# l298_updated.net
KiCad netlist of a schematic drawn in EAGLE
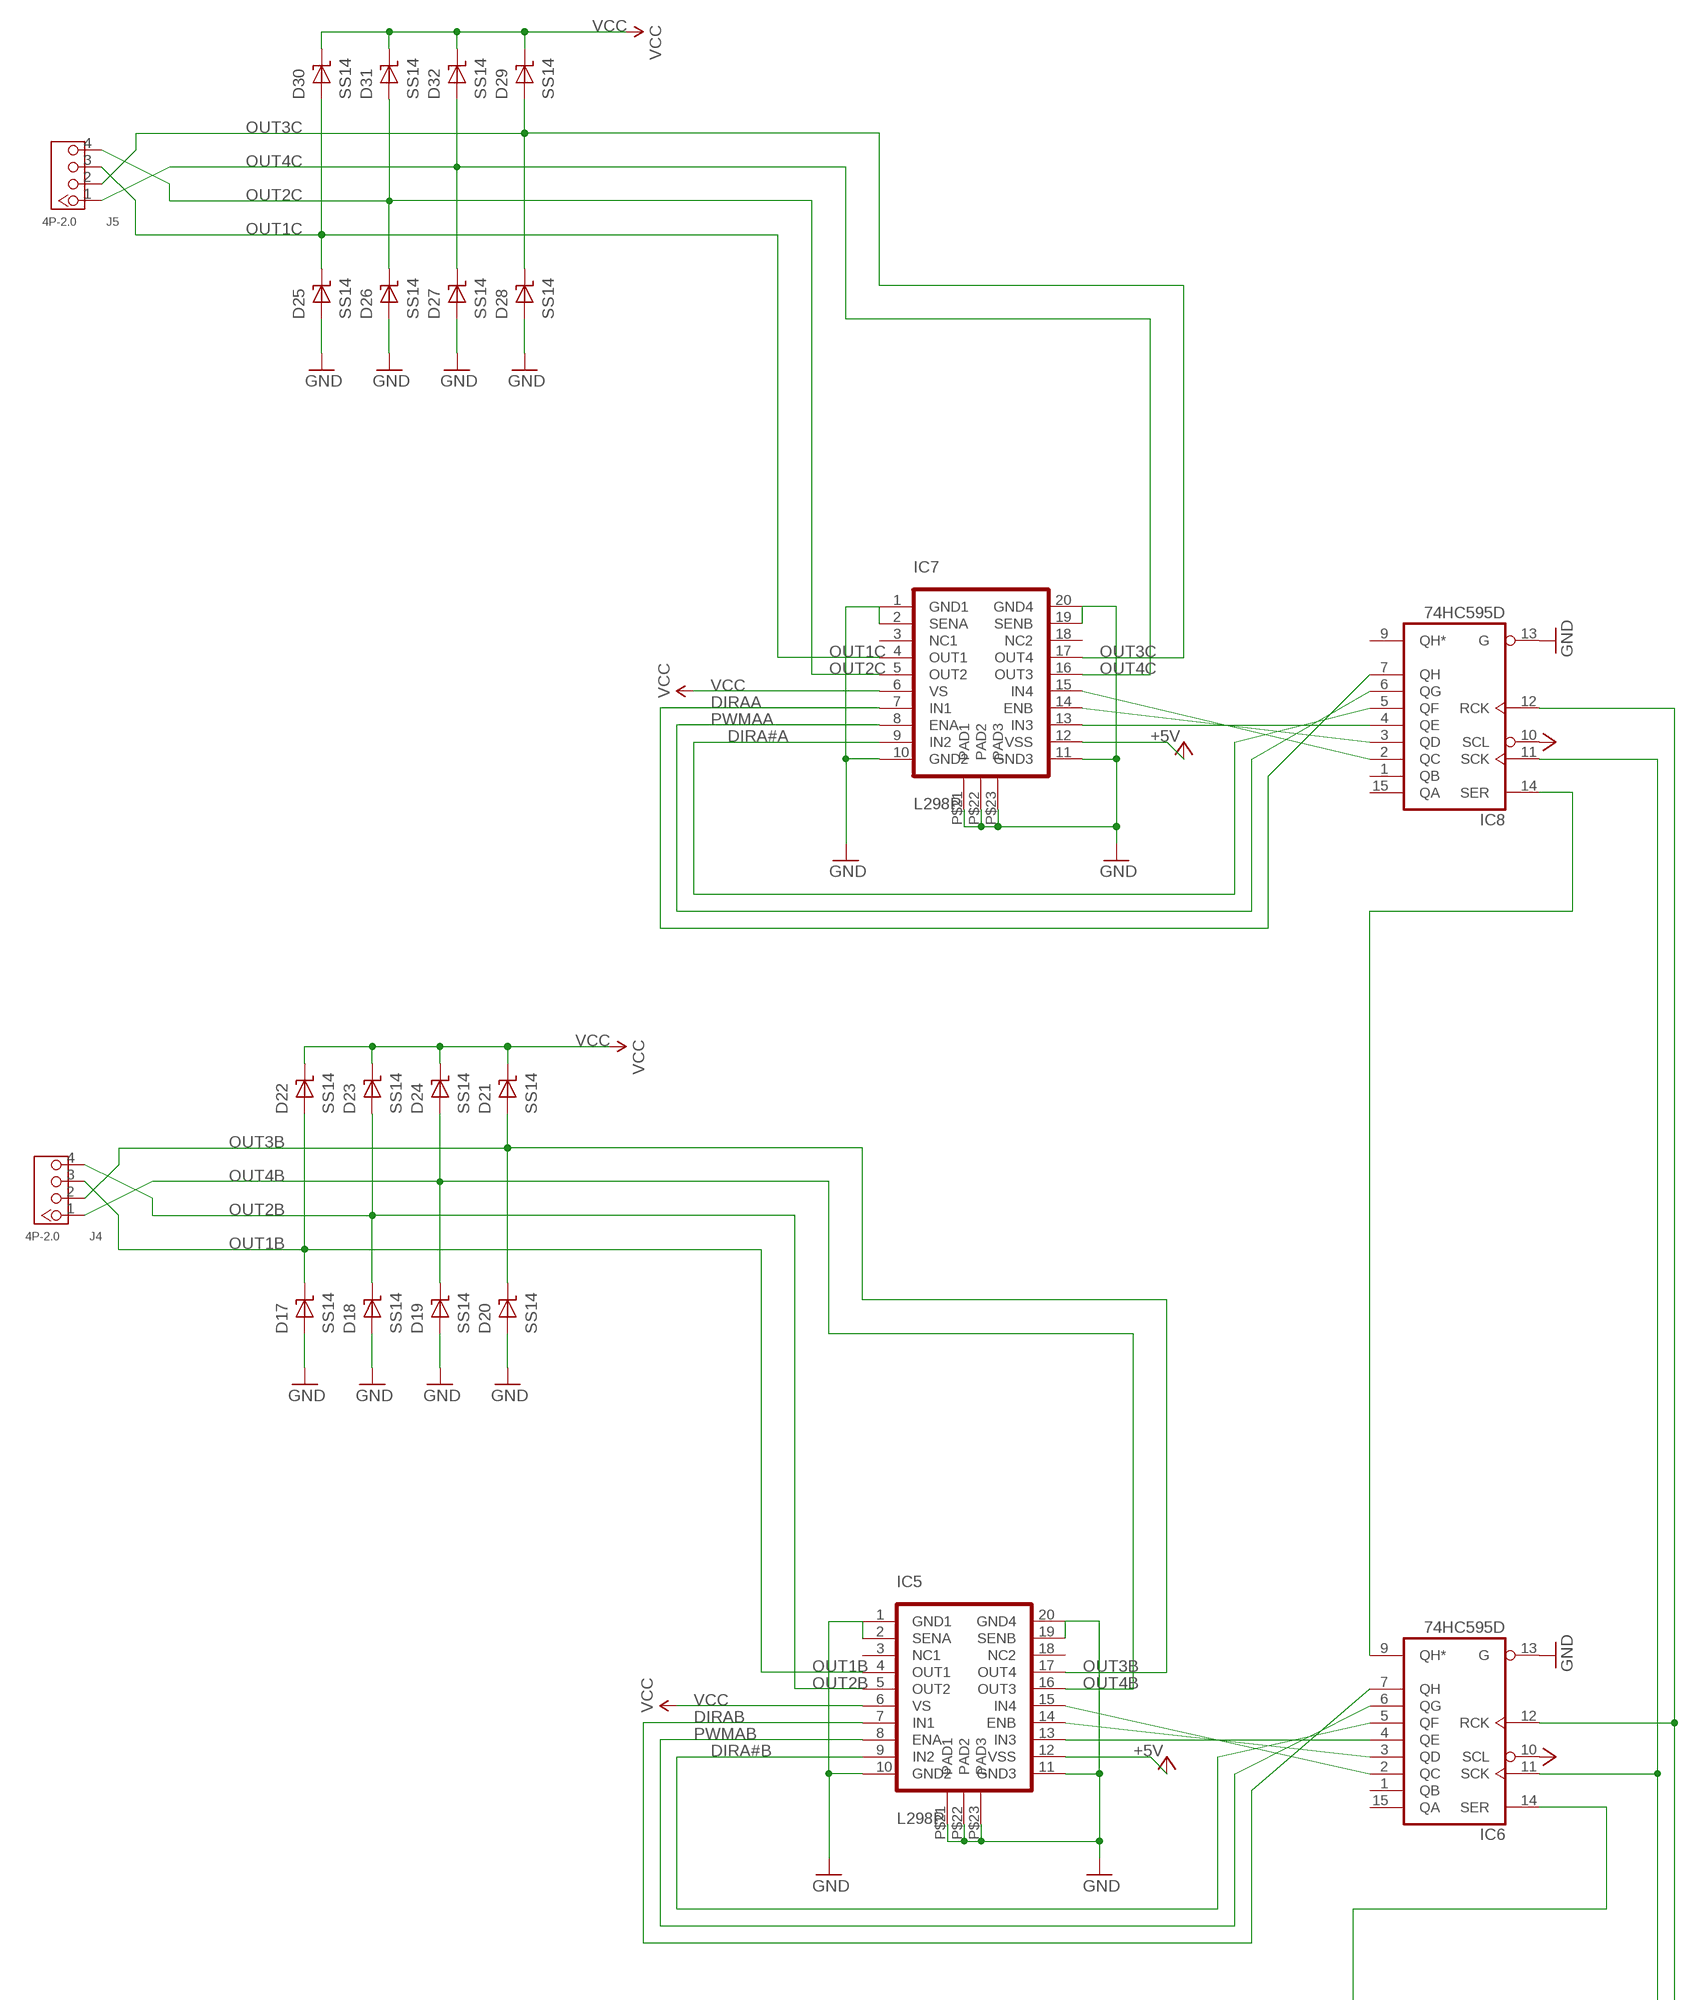
[diagram p0: schematic, sheet 1, part 1 of 2]
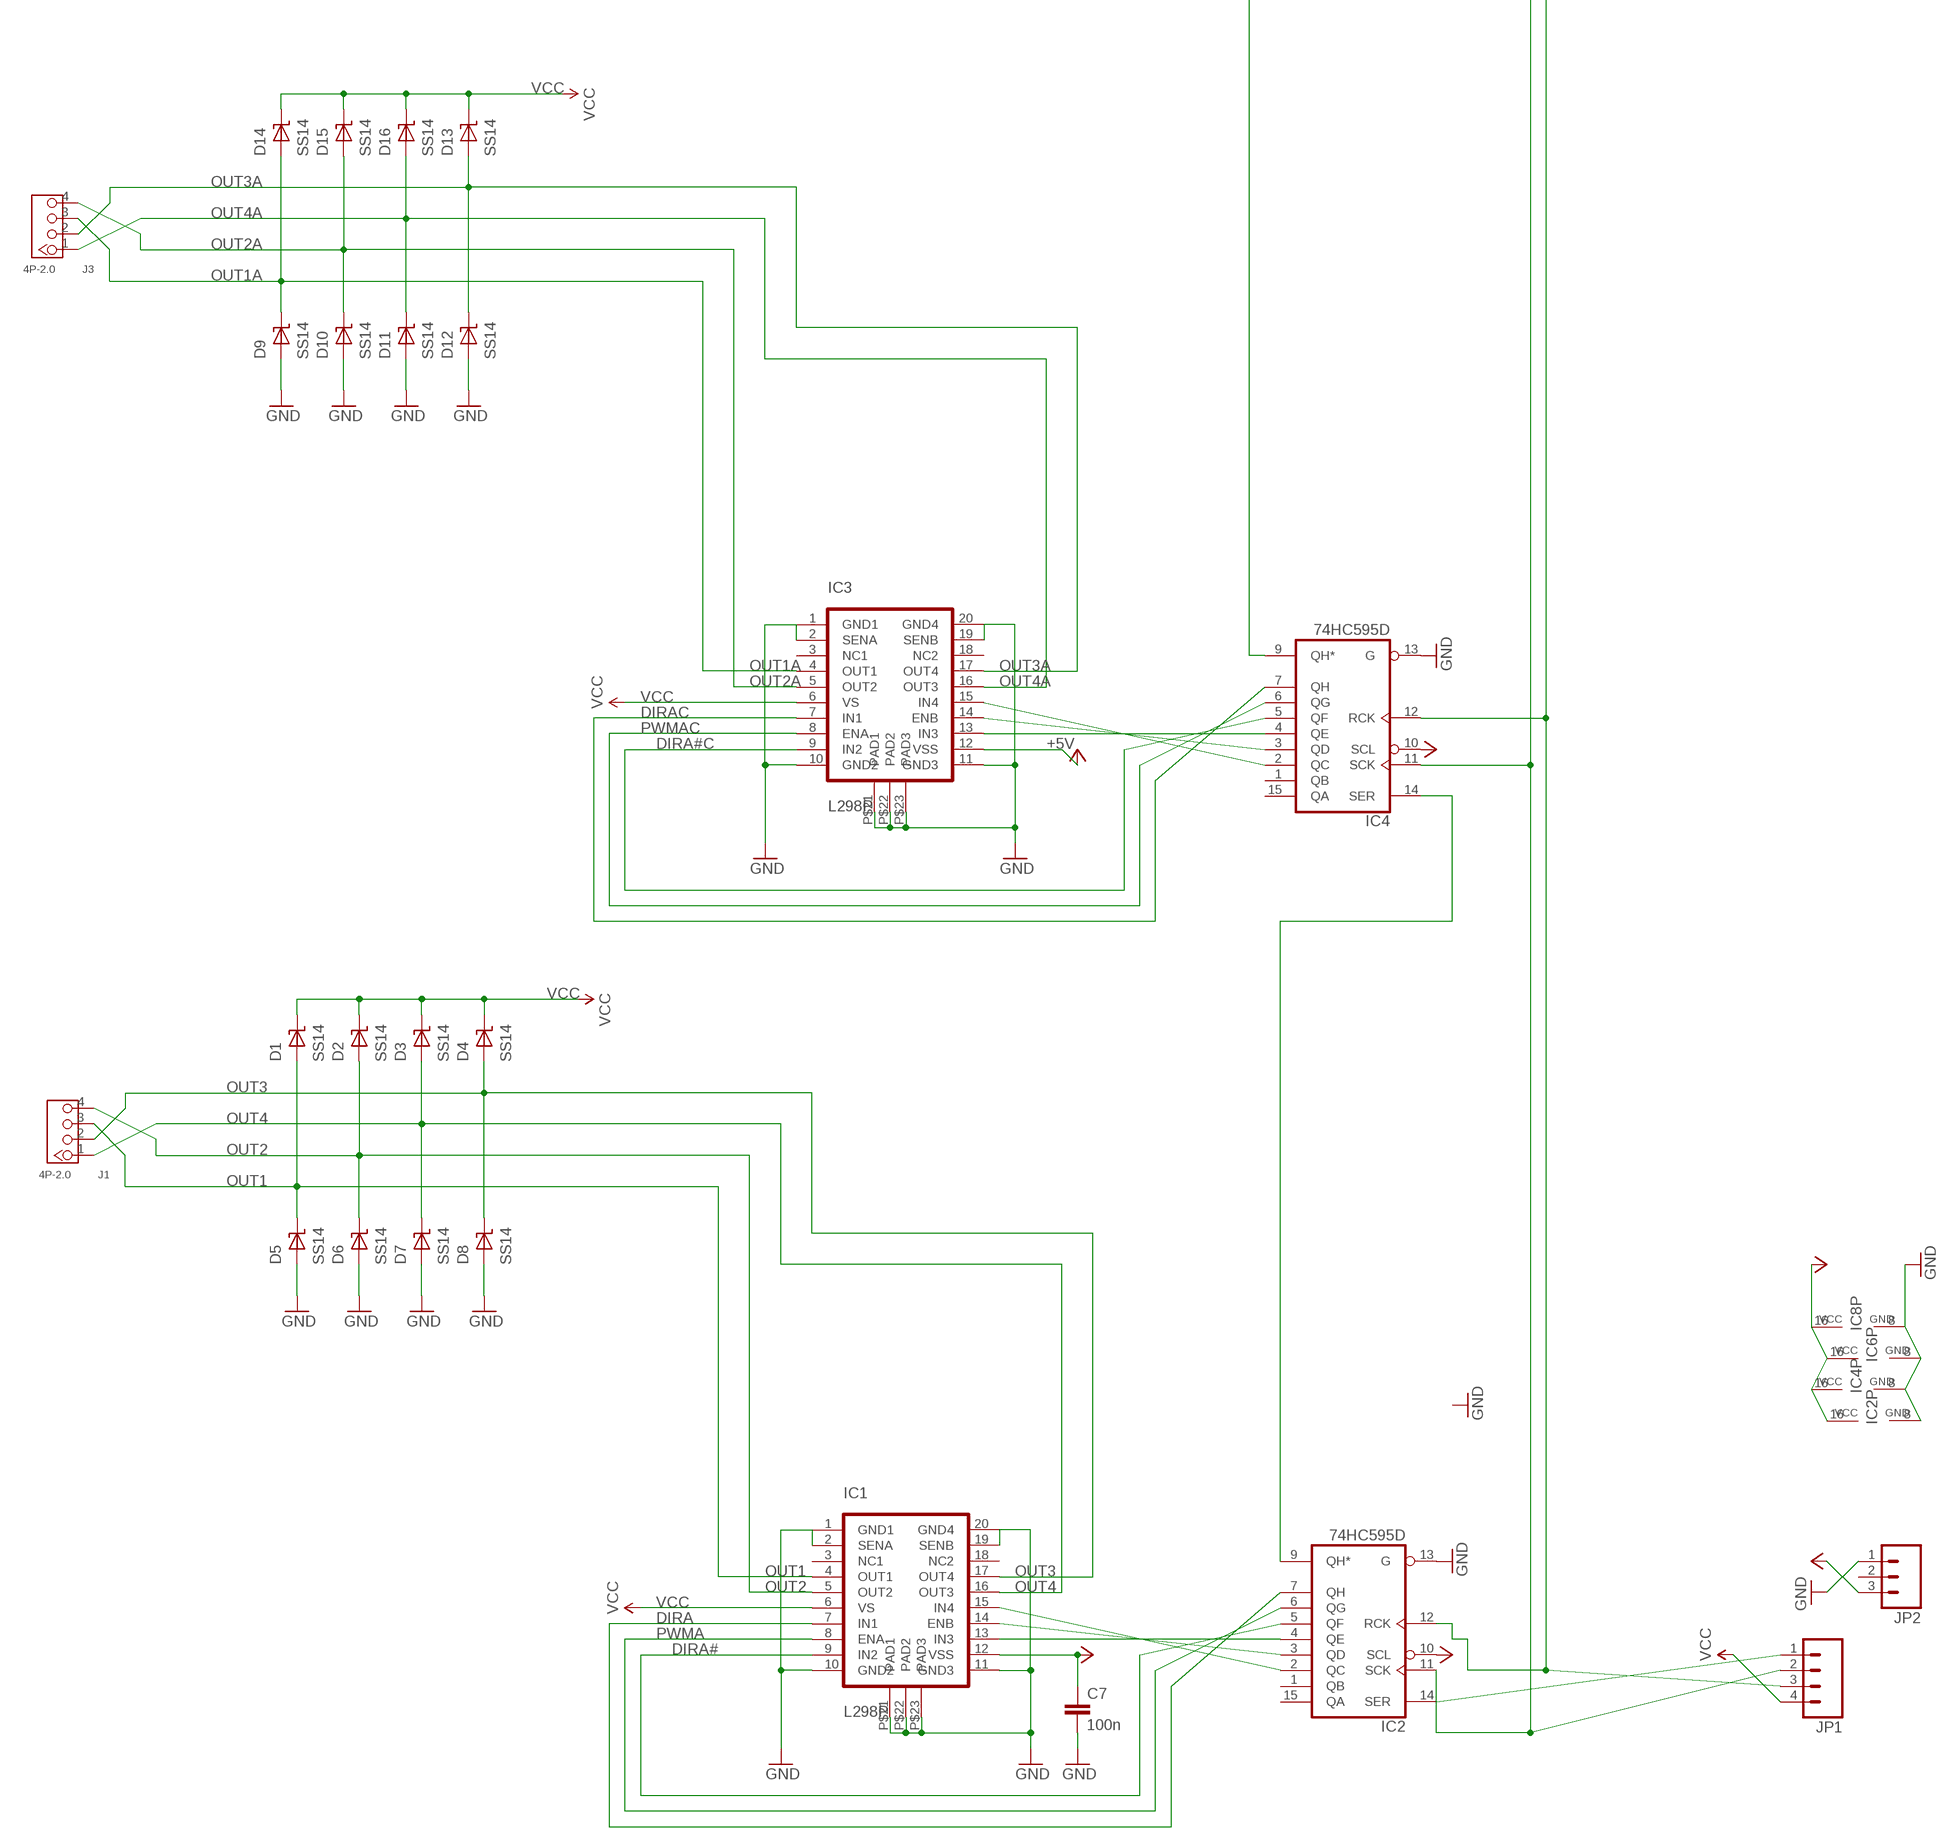
[diagram p1: schematic, sheet 1, part 2 of 2]

(export (version "E")
  (design (tool "Eeschema 10.0.6"))
  (components
    (comp (ref "C7")
      (value "100n")
      (footprint "eagle-import:C0603-ROUND")
      (libsource (lib "eagle-import") (part "C-EUC0603"))
    )
    (comp (ref "D1")
      (value "SS14")
      (footprint "eagle-import:SMA")
      (libsource (lib "eagle-import") (part "SS14"))
    )
    (comp (ref "D2")
      (value "SS14")
      (footprint "eagle-import:SMA")
      (libsource (lib "eagle-import") (part "SS14"))
    )
    (comp (ref "D3")
      (value "SS14")
      (footprint "eagle-import:SMA")
      (libsource (lib "eagle-import") (part "SS14"))
    )
    (comp (ref "D4")
      (value "SS14")
      (footprint "eagle-import:SMA")
      (libsource (lib "eagle-import") (part "SS14"))
    )
    (comp (ref "D5")
      (value "SS14")
      (footprint "eagle-import:SMA")
      (libsource (lib "eagle-import") (part "SS14"))
    )
    (comp (ref "D6")
      (value "SS14")
      (footprint "eagle-import:SMA")
      (libsource (lib "eagle-import") (part "SS14"))
    )
    (comp (ref "D7")
      (value "SS14")
      (footprint "eagle-import:SMA")
      (libsource (lib "eagle-import") (part "SS14"))
    )
    (comp (ref "D8")
      (value "SS14")
      (footprint "eagle-import:SMA")
      (libsource (lib "eagle-import") (part "SS14"))
    )
    (comp (ref "D9")
      (value "SS14")
      (footprint "eagle-import:SMA")
      (libsource (lib "eagle-import") (part "SS14"))
    )
    (comp (ref "D10")
      (value "SS14")
      (footprint "eagle-import:SMA")
      (libsource (lib "eagle-import") (part "SS14"))
    )
    (comp (ref "D11")
      (value "SS14")
      (footprint "eagle-import:SMA")
      (libsource (lib "eagle-import") (part "SS14"))
    )
    (comp (ref "D12")
      (value "SS14")
      (footprint "eagle-import:SMA")
      (libsource (lib "eagle-import") (part "SS14"))
    )
    (comp (ref "D13")
      (value "SS14")
      (footprint "eagle-import:SMA")
      (libsource (lib "eagle-import") (part "SS14"))
    )
    (comp (ref "D14")
      (value "SS14")
      (footprint "eagle-import:SMA")
      (libsource (lib "eagle-import") (part "SS14"))
    )
    (comp (ref "D15")
      (value "SS14")
      (footprint "eagle-import:SMA")
      (libsource (lib "eagle-import") (part "SS14"))
    )
    (comp (ref "D16")
      (value "SS14")
      (footprint "eagle-import:SMA")
      (libsource (lib "eagle-import") (part "SS14"))
    )
    (comp (ref "D17")
      (value "SS14")
      (footprint "eagle-import:SMA")
      (libsource (lib "eagle-import") (part "SS14"))
    )
    (comp (ref "D18")
      (value "SS14")
      (footprint "eagle-import:SMA")
      (libsource (lib "eagle-import") (part "SS14"))
    )
    (comp (ref "D19")
      (value "SS14")
      (footprint "eagle-import:SMA")
      (libsource (lib "eagle-import") (part "SS14"))
    )
    (comp (ref "D20")
      (value "SS14")
      (footprint "eagle-import:SMA")
      (libsource (lib "eagle-import") (part "SS14"))
    )
    (comp (ref "D21")
      (value "SS14")
      (footprint "eagle-import:SMA")
      (libsource (lib "eagle-import") (part "SS14"))
    )
    (comp (ref "D22")
      (value "SS14")
      (footprint "eagle-import:SMA")
      (libsource (lib "eagle-import") (part "SS14"))
    )
    (comp (ref "D23")
      (value "SS14")
      (footprint "eagle-import:SMA")
      (libsource (lib "eagle-import") (part "SS14"))
    )
    (comp (ref "D24")
      (value "SS14")
      (footprint "eagle-import:SMA")
      (libsource (lib "eagle-import") (part "SS14"))
    )
    (comp (ref "D25")
      (value "SS14")
      (footprint "eagle-import:SMA")
      (libsource (lib "eagle-import") (part "SS14"))
    )
    (comp (ref "D26")
      (value "SS14")
      (footprint "eagle-import:SMA")
      (libsource (lib "eagle-import") (part "SS14"))
    )
    (comp (ref "D27")
      (value "SS14")
      (footprint "eagle-import:SMA")
      (libsource (lib "eagle-import") (part "SS14"))
    )
    (comp (ref "D28")
      (value "SS14")
      (footprint "eagle-import:SMA")
      (libsource (lib "eagle-import") (part "SS14"))
    )
    (comp (ref "D29")
      (value "SS14")
      (footprint "eagle-import:SMA")
      (libsource (lib "eagle-import") (part "SS14"))
    )
    (comp (ref "D30")
      (value "SS14")
      (footprint "eagle-import:SMA")
      (libsource (lib "eagle-import") (part "SS14"))
    )
    (comp (ref "D31")
      (value "SS14")
      (footprint "eagle-import:SMA")
      (libsource (lib "eagle-import") (part "SS14"))
    )
    (comp (ref "D32")
      (value "SS14")
      (footprint "eagle-import:SMA")
      (libsource (lib "eagle-import") (part "SS14"))
    )
    (comp (ref "IC1")
      (value "L298P")
      (footprint "eagle-import:POWER-SO20")
      (libsource (lib "eagle-import") (part "L298P"))
    )
    (comp (ref "IC2")
      (value "74HC595D")
      (footprint "eagle-import:SO16")
      (libsource (lib "eagle-import") (part "74595DHC"))
    )
    (comp (ref "IC3")
      (value "L298P")
      (footprint "eagle-import:POWER-SO20")
      (libsource (lib "eagle-import") (part "L298P"))
    )
    (comp (ref "IC4")
      (value "74HC595D")
      (footprint "eagle-import:SO16")
      (libsource (lib "eagle-import") (part "74595DHC"))
    )
    (comp (ref "IC5")
      (value "L298P")
      (footprint "eagle-import:POWER-SO20")
      (libsource (lib "eagle-import") (part "L298P"))
    )
    (comp (ref "IC6")
      (value "74HC595D")
      (footprint "eagle-import:SO16")
      (libsource (lib "eagle-import") (part "74595DHC"))
    )
    (comp (ref "IC7")
      (value "L298P")
      (footprint "eagle-import:POWER-SO20")
      (libsource (lib "eagle-import") (part "L298P"))
    )
    (comp (ref "IC8")
      (value "74HC595D")
      (footprint "eagle-import:SO16")
      (libsource (lib "eagle-import") (part "74595DHC"))
    )
    (comp (ref "J1")
      (value "4P-2.0")
      (footprint "eagle-import:HW4-2.0")
      (libsource (lib "eagle-import") (part "GROVE-CONNECTOR-DIP(4P-2.0)"))
    )
    (comp (ref "J3")
      (value "4P-2.0")
      (footprint "eagle-import:HW4-2.0")
      (libsource (lib "eagle-import") (part "GROVE-CONNECTOR-DIP(4P-2.0)"))
    )
    (comp (ref "J4")
      (value "4P-2.0")
      (footprint "eagle-import:HW4-2.0")
      (libsource (lib "eagle-import") (part "GROVE-CONNECTOR-DIP(4P-2.0)"))
    )
    (comp (ref "J5")
      (value "4P-2.0")
      (footprint "eagle-import:HW4-2.0")
      (libsource (lib "eagle-import") (part "GROVE-CONNECTOR-DIP(4P-2.0)"))
    )
    (comp (ref "JP1")
      (value "M04PTH")
      (footprint "eagle-import:1X04")
      (libsource (lib "eagle-import") (part "M04PTH"))
    )
    (comp (ref "JP2")
      (value "M03PTH")
      (footprint "eagle-import:1X03")
      (libsource (lib "eagle-import") (part "M03PTH"))
    )
  )
  (nets
    (net (code "1") (name "+5V") (class "Default")
      (node (ref "C7") (pin "1") (pinfunction "1_1") (pintype "passive"))
      (node (ref "IC1") (pin "P$12") (pinfunction "VSS_P$12") (pintype "power_in"))
      (node (ref "IC2") (pin "10") (pinfunction "SCL_10") (pintype "input"))
      (node (ref "IC2") (pin "16") (pinfunction "VCC_16") (pintype "power_in"))
      (node (ref "IC3") (pin "P$12") (pinfunction "VSS_P$12") (pintype "power_in"))
      (node (ref "IC4") (pin "10") (pinfunction "SCL_10") (pintype "input"))
      (node (ref "IC4") (pin "16") (pinfunction "VCC_16") (pintype "power_in"))
      (node (ref "IC5") (pin "P$12") (pinfunction "VSS_P$12") (pintype "power_in"))
      (node (ref "IC6") (pin "10") (pinfunction "SCL_10") (pintype "input"))
      (node (ref "IC6") (pin "16") (pinfunction "VCC_16") (pintype "power_in"))
      (node (ref "IC7") (pin "P$12") (pinfunction "VSS_P$12") (pintype "power_in"))
      (node (ref "IC8") (pin "10") (pinfunction "SCL_10") (pintype "input"))
      (node (ref "IC8") (pin "16") (pinfunction "VCC_16") (pintype "power_in"))
      (node (ref "JP2") (pin "3") (pinfunction "3_3") (pintype "passive"))
    )
    (net (code "2") (name "/DIRA") (class "Default")
      (node (ref "IC1") (pin "P$7") (pinfunction "IN1_P$7") (pintype "input"))
      (node (ref "IC2") (pin "7") (pinfunction "QH_7") (pintype "tri_state"))
    )
    (net (code "3") (name "/DIRA#") (class "Default")
      (node (ref "IC1") (pin "P$9") (pinfunction "IN2_P$9") (pintype "input"))
      (node (ref "IC2") (pin "5") (pinfunction "QF_5") (pintype "tri_state"))
    )
    (net (code "4") (name "/DIRA#A") (class "Default")
      (node (ref "IC7") (pin "P$9") (pinfunction "IN2_P$9") (pintype "input"))
      (node (ref "IC8") (pin "5") (pinfunction "QF_5") (pintype "tri_state"))
    )
    (net (code "5") (name "/DIRA#B") (class "Default")
      (node (ref "IC5") (pin "P$9") (pinfunction "IN2_P$9") (pintype "input"))
      (node (ref "IC6") (pin "5") (pinfunction "QF_5") (pintype "tri_state"))
    )
    (net (code "6") (name "/DIRA#C") (class "Default")
      (node (ref "IC3") (pin "P$9") (pinfunction "IN2_P$9") (pintype "input"))
      (node (ref "IC4") (pin "5") (pinfunction "QF_5") (pintype "tri_state"))
    )
    (net (code "7") (name "/DIRAA") (class "Default")
      (node (ref "IC7") (pin "P$7") (pinfunction "IN1_P$7") (pintype "input"))
      (node (ref "IC8") (pin "7") (pinfunction "QH_7") (pintype "tri_state"))
    )
    (net (code "8") (name "/DIRAB") (class "Default")
      (node (ref "IC5") (pin "P$7") (pinfunction "IN1_P$7") (pintype "input"))
      (node (ref "IC6") (pin "7") (pinfunction "QH_7") (pintype "tri_state"))
    )
    (net (code "9") (name "/DIRAC") (class "Default")
      (node (ref "IC3") (pin "P$7") (pinfunction "IN1_P$7") (pintype "input"))
      (node (ref "IC4") (pin "7") (pinfunction "QH_7") (pintype "tri_state"))
    )
    (net (code "10") (name "/OUT1") (class "Default")
      (node (ref "D1") (pin "P$2") (pinfunction "A_P$2") (pintype "bidirectional"))
      (node (ref "D5") (pin "P$1") (pinfunction "K_P$1") (pintype "bidirectional"))
      (node (ref "IC1") (pin "P$4") (pinfunction "OUT1_P$4") (pintype "output"))
      (node (ref "J1") (pin "3") (pinfunction "3_3") (pintype "bidirectional"))
    )
    (net (code "11") (name "/OUT1A") (class "Default")
      (node (ref "D14") (pin "P$2") (pinfunction "A_P$2") (pintype "bidirectional"))
      (node (ref "D9") (pin "P$1") (pinfunction "K_P$1") (pintype "bidirectional"))
      (node (ref "IC3") (pin "P$4") (pinfunction "OUT1_P$4") (pintype "output"))
      (node (ref "J3") (pin "3") (pinfunction "3_3") (pintype "bidirectional"))
    )
    (net (code "12") (name "/OUT1B") (class "Default")
      (node (ref "D17") (pin "P$1") (pinfunction "K_P$1") (pintype "bidirectional"))
      (node (ref "D22") (pin "P$2") (pinfunction "A_P$2") (pintype "bidirectional"))
      (node (ref "IC5") (pin "P$4") (pinfunction "OUT1_P$4") (pintype "output"))
      (node (ref "J4") (pin "3") (pinfunction "3_3") (pintype "bidirectional"))
    )
    (net (code "13") (name "/OUT1C") (class "Default")
      (node (ref "D25") (pin "P$1") (pinfunction "K_P$1") (pintype "bidirectional"))
      (node (ref "D30") (pin "P$2") (pinfunction "A_P$2") (pintype "bidirectional"))
      (node (ref "IC7") (pin "P$4") (pinfunction "OUT1_P$4") (pintype "output"))
      (node (ref "J5") (pin "3") (pinfunction "3_3") (pintype "bidirectional"))
    )
    (net (code "14") (name "/OUT2") (class "Default")
      (node (ref "D2") (pin "P$2") (pinfunction "A_P$2") (pintype "bidirectional"))
      (node (ref "D6") (pin "P$1") (pinfunction "K_P$1") (pintype "bidirectional"))
      (node (ref "IC1") (pin "P$5") (pinfunction "OUT2_P$5") (pintype "output"))
      (node (ref "J1") (pin "4") (pinfunction "4_4") (pintype "bidirectional"))
    )
    (net (code "15") (name "/OUT2A") (class "Default")
      (node (ref "D10") (pin "P$1") (pinfunction "K_P$1") (pintype "bidirectional"))
      (node (ref "D15") (pin "P$2") (pinfunction "A_P$2") (pintype "bidirectional"))
      (node (ref "IC3") (pin "P$5") (pinfunction "OUT2_P$5") (pintype "output"))
      (node (ref "J3") (pin "4") (pinfunction "4_4") (pintype "bidirectional"))
    )
    (net (code "16") (name "/OUT2B") (class "Default")
      (node (ref "D18") (pin "P$1") (pinfunction "K_P$1") (pintype "bidirectional"))
      (node (ref "D23") (pin "P$2") (pinfunction "A_P$2") (pintype "bidirectional"))
      (node (ref "IC5") (pin "P$5") (pinfunction "OUT2_P$5") (pintype "output"))
      (node (ref "J4") (pin "4") (pinfunction "4_4") (pintype "bidirectional"))
    )
    (net (code "17") (name "/OUT2C") (class "Default")
      (node (ref "D26") (pin "P$1") (pinfunction "K_P$1") (pintype "bidirectional"))
      (node (ref "D31") (pin "P$2") (pinfunction "A_P$2") (pintype "bidirectional"))
      (node (ref "IC7") (pin "P$5") (pinfunction "OUT2_P$5") (pintype "output"))
      (node (ref "J5") (pin "4") (pinfunction "4_4") (pintype "bidirectional"))
    )
    (net (code "18") (name "/OUT3") (class "Default")
      (node (ref "D4") (pin "P$2") (pinfunction "A_P$2") (pintype "bidirectional"))
      (node (ref "D8") (pin "P$1") (pinfunction "K_P$1") (pintype "bidirectional"))
      (node (ref "IC1") (pin "P$17") (pinfunction "OUT4_P$17") (pintype "output"))
      (node (ref "J1") (pin "2") (pinfunction "2_2") (pintype "bidirectional"))
    )
    (net (code "19") (name "/OUT3A") (class "Default")
      (node (ref "D12") (pin "P$1") (pinfunction "K_P$1") (pintype "bidirectional"))
      (node (ref "D13") (pin "P$2") (pinfunction "A_P$2") (pintype "bidirectional"))
      (node (ref "IC3") (pin "P$17") (pinfunction "OUT4_P$17") (pintype "output"))
      (node (ref "J3") (pin "2") (pinfunction "2_2") (pintype "bidirectional"))
    )
    (net (code "20") (name "/OUT3B") (class "Default")
      (node (ref "D20") (pin "P$1") (pinfunction "K_P$1") (pintype "bidirectional"))
      (node (ref "D21") (pin "P$2") (pinfunction "A_P$2") (pintype "bidirectional"))
      (node (ref "IC5") (pin "P$17") (pinfunction "OUT4_P$17") (pintype "output"))
      (node (ref "J4") (pin "2") (pinfunction "2_2") (pintype "bidirectional"))
    )
    (net (code "21") (name "/OUT3C") (class "Default")
      (node (ref "D28") (pin "P$1") (pinfunction "K_P$1") (pintype "bidirectional"))
      (node (ref "D29") (pin "P$2") (pinfunction "A_P$2") (pintype "bidirectional"))
      (node (ref "IC7") (pin "P$17") (pinfunction "OUT4_P$17") (pintype "output"))
      (node (ref "J5") (pin "2") (pinfunction "2_2") (pintype "bidirectional"))
    )
    (net (code "22") (name "/OUT4") (class "Default")
      (node (ref "D3") (pin "P$2") (pinfunction "A_P$2") (pintype "bidirectional"))
      (node (ref "D7") (pin "P$1") (pinfunction "K_P$1") (pintype "bidirectional"))
      (node (ref "IC1") (pin "P$16") (pinfunction "OUT3_P$16") (pintype "output"))
      (node (ref "J1") (pin "1") (pinfunction "1_1") (pintype "bidirectional"))
    )
    (net (code "23") (name "/OUT4A") (class "Default")
      (node (ref "D11") (pin "P$1") (pinfunction "K_P$1") (pintype "bidirectional"))
      (node (ref "D16") (pin "P$2") (pinfunction "A_P$2") (pintype "bidirectional"))
      (node (ref "IC3") (pin "P$16") (pinfunction "OUT3_P$16") (pintype "output"))
      (node (ref "J3") (pin "1") (pinfunction "1_1") (pintype "bidirectional"))
    )
    (net (code "24") (name "/OUT4B") (class "Default")
      (node (ref "D19") (pin "P$1") (pinfunction "K_P$1") (pintype "bidirectional"))
      (node (ref "D24") (pin "P$2") (pinfunction "A_P$2") (pintype "bidirectional"))
      (node (ref "IC5") (pin "P$16") (pinfunction "OUT3_P$16") (pintype "output"))
      (node (ref "J4") (pin "1") (pinfunction "1_1") (pintype "bidirectional"))
    )
    (net (code "25") (name "/OUT4C") (class "Default")
      (node (ref "D27") (pin "P$1") (pinfunction "K_P$1") (pintype "bidirectional"))
      (node (ref "D32") (pin "P$2") (pinfunction "A_P$2") (pintype "bidirectional"))
      (node (ref "IC7") (pin "P$16") (pinfunction "OUT3_P$16") (pintype "output"))
      (node (ref "J5") (pin "1") (pinfunction "1_1") (pintype "bidirectional"))
    )
    (net (code "26") (name "/PWMA") (class "Default")
      (node (ref "IC1") (pin "P$8") (pinfunction "ENA_P$8") (pintype "input"))
      (node (ref "IC2") (pin "6") (pinfunction "QG_6") (pintype "tri_state"))
    )
    (net (code "27") (name "/PWMAA") (class "Default")
      (node (ref "IC7") (pin "P$8") (pinfunction "ENA_P$8") (pintype "input"))
      (node (ref "IC8") (pin "6") (pinfunction "QG_6") (pintype "tri_state"))
    )
    (net (code "28") (name "/PWMAB") (class "Default")
      (node (ref "IC5") (pin "P$8") (pinfunction "ENA_P$8") (pintype "input"))
      (node (ref "IC6") (pin "6") (pinfunction "QG_6") (pintype "tri_state"))
    )
    (net (code "29") (name "/PWMAC") (class "Default")
      (node (ref "IC3") (pin "P$8") (pinfunction "ENA_P$8") (pintype "input"))
      (node (ref "IC4") (pin "6") (pinfunction "QG_6") (pintype "tri_state"))
    )
    (net (code "30") (name "GND") (class "Default")
      (node (ref "C7") (pin "2") (pinfunction "2_2") (pintype "passive"))
      (node (ref "D10") (pin "P$2") (pinfunction "A_P$2") (pintype "bidirectional"))
      (node (ref "D11") (pin "P$2") (pinfunction "A_P$2") (pintype "bidirectional"))
      (node (ref "D12") (pin "P$2") (pinfunction "A_P$2") (pintype "bidirectional"))
      (node (ref "D17") (pin "P$2") (pinfunction "A_P$2") (pintype "bidirectional"))
      (node (ref "D18") (pin "P$2") (pinfunction "A_P$2") (pintype "bidirectional"))
      (node (ref "D19") (pin "P$2") (pinfunction "A_P$2") (pintype "bidirectional"))
      (node (ref "D20") (pin "P$2") (pinfunction "A_P$2") (pintype "bidirectional"))
      (node (ref "D25") (pin "P$2") (pinfunction "A_P$2") (pintype "bidirectional"))
      (node (ref "D26") (pin "P$2") (pinfunction "A_P$2") (pintype "bidirectional"))
      (node (ref "D27") (pin "P$2") (pinfunction "A_P$2") (pintype "bidirectional"))
      (node (ref "D28") (pin "P$2") (pinfunction "A_P$2") (pintype "bidirectional"))
      (node (ref "D5") (pin "P$2") (pinfunction "A_P$2") (pintype "bidirectional"))
      (node (ref "D6") (pin "P$2") (pinfunction "A_P$2") (pintype "bidirectional"))
      (node (ref "D7") (pin "P$2") (pinfunction "A_P$2") (pintype "bidirectional"))
      (node (ref "D8") (pin "P$2") (pinfunction "A_P$2") (pintype "bidirectional"))
      (node (ref "D9") (pin "P$2") (pinfunction "A_P$2") (pintype "bidirectional"))
      (node (ref "IC1") (pin "P$1") (pinfunction "GND1_P$1") (pintype "power_in"))
      (node (ref "IC1") (pin "P$10") (pinfunction "GND2_P$10") (pintype "power_in"))
      (node (ref "IC1") (pin "P$11") (pinfunction "GND3_P$11") (pintype "power_in"))
      (node (ref "IC1") (pin "P$19") (pinfunction "SENB_P$19") (pintype "input"))
      (node (ref "IC1") (pin "P$2") (pinfunction "SENA_P$2") (pintype "input"))
      (node (ref "IC1") (pin "P$20") (pinfunction "GND4_P$20") (pintype "power_in"))
      (node (ref "IC1") (pin "P$21") (pinfunction "PAD1_P$21") (pintype "passive"))
      (node (ref "IC1") (pin "P$22") (pinfunction "PAD2_P$22") (pintype "passive"))
      (node (ref "IC1") (pin "P$23") (pinfunction "PAD3_P$23") (pintype "passive"))
      (node (ref "IC2") (pin "13") (pinfunction "G_13") (pintype "input"))
      (node (ref "IC2") (pin "8") (pinfunction "GND_8") (pintype "power_in"))
      (node (ref "IC3") (pin "P$1") (pinfunction "GND1_P$1") (pintype "power_in"))
      (node (ref "IC3") (pin "P$10") (pinfunction "GND2_P$10") (pintype "power_in"))
      (node (ref "IC3") (pin "P$11") (pinfunction "GND3_P$11") (pintype "power_in"))
      (node (ref "IC3") (pin "P$19") (pinfunction "SENB_P$19") (pintype "input"))
      (node (ref "IC3") (pin "P$2") (pinfunction "SENA_P$2") (pintype "input"))
      (node (ref "IC3") (pin "P$20") (pinfunction "GND4_P$20") (pintype "power_in"))
      (node (ref "IC3") (pin "P$21") (pinfunction "PAD1_P$21") (pintype "passive"))
      (node (ref "IC3") (pin "P$22") (pinfunction "PAD2_P$22") (pintype "passive"))
      (node (ref "IC3") (pin "P$23") (pinfunction "PAD3_P$23") (pintype "passive"))
      (node (ref "IC4") (pin "13") (pinfunction "G_13") (pintype "input"))
      (node (ref "IC4") (pin "8") (pinfunction "GND_8") (pintype "power_in"))
      (node (ref "IC5") (pin "P$1") (pinfunction "GND1_P$1") (pintype "power_in"))
      (node (ref "IC5") (pin "P$10") (pinfunction "GND2_P$10") (pintype "power_in"))
      (node (ref "IC5") (pin "P$11") (pinfunction "GND3_P$11") (pintype "power_in"))
      (node (ref "IC5") (pin "P$19") (pinfunction "SENB_P$19") (pintype "input"))
      (node (ref "IC5") (pin "P$2") (pinfunction "SENA_P$2") (pintype "input"))
      (node (ref "IC5") (pin "P$20") (pinfunction "GND4_P$20") (pintype "power_in"))
      (node (ref "IC5") (pin "P$21") (pinfunction "PAD1_P$21") (pintype "passive"))
      (node (ref "IC5") (pin "P$22") (pinfunction "PAD2_P$22") (pintype "passive"))
      (node (ref "IC5") (pin "P$23") (pinfunction "PAD3_P$23") (pintype "passive"))
      (node (ref "IC6") (pin "13") (pinfunction "G_13") (pintype "input"))
      (node (ref "IC6") (pin "8") (pinfunction "GND_8") (pintype "power_in"))
      (node (ref "IC7") (pin "P$1") (pinfunction "GND1_P$1") (pintype "power_in"))
      (node (ref "IC7") (pin "P$10") (pinfunction "GND2_P$10") (pintype "power_in"))
      (node (ref "IC7") (pin "P$11") (pinfunction "GND3_P$11") (pintype "power_in"))
      (node (ref "IC7") (pin "P$19") (pinfunction "SENB_P$19") (pintype "input"))
      (node (ref "IC7") (pin "P$2") (pinfunction "SENA_P$2") (pintype "input"))
      (node (ref "IC7") (pin "P$20") (pinfunction "GND4_P$20") (pintype "power_in"))
      (node (ref "IC7") (pin "P$21") (pinfunction "PAD1_P$21") (pintype "passive"))
      (node (ref "IC7") (pin "P$22") (pinfunction "PAD2_P$22") (pintype "passive"))
      (node (ref "IC7") (pin "P$23") (pinfunction "PAD3_P$23") (pintype "passive"))
      (node (ref "IC8") (pin "13") (pinfunction "G_13") (pintype "input"))
      (node (ref "IC8") (pin "8") (pinfunction "GND_8") (pintype "power_in"))
      (node (ref "JP2") (pin "1") (pinfunction "1_1") (pintype "passive"))
    )
    (net (code "31") (name "Net-(IC1-ENB)") (class "Default")
      (node (ref "IC1") (pin "P$14") (pinfunction "ENB_P$14") (pintype "input"))
      (node (ref "IC2") (pin "3") (pinfunction "QD_3") (pintype "tri_state"))
    )
    (net (code "32") (name "Net-(IC1-IN3)") (class "Default")
      (node (ref "IC1") (pin "P$13") (pinfunction "IN3_P$13") (pintype "input"))
      (node (ref "IC2") (pin "4") (pinfunction "QE_4") (pintype "tri_state"))
    )
    (net (code "33") (name "Net-(IC1-IN4)") (class "Default")
      (node (ref "IC1") (pin "P$15") (pinfunction "IN4_P$15") (pintype "input"))
      (node (ref "IC2") (pin "2") (pinfunction "QC_2") (pintype "tri_state"))
    )
    (net (code "34") (name "Net-(IC2A-QH*)") (class "Default")
      (node (ref "IC2") (pin "9") (pinfunction "QH*_9") (pintype "tri_state"))
      (node (ref "IC4") (pin "14") (pinfunction "SER_14") (pintype "input"))
    )
    (net (code "35") (name "Net-(IC2A-RCK)") (class "Default")
      (node (ref "IC2") (pin "12") (pinfunction "RCK_12") (pintype "input"))
      (node (ref "IC4") (pin "12") (pinfunction "RCK_12") (pintype "input"))
      (node (ref "IC6") (pin "12") (pinfunction "RCK_12") (pintype "input"))
      (node (ref "IC8") (pin "12") (pinfunction "RCK_12") (pintype "input"))
      (node (ref "JP1") (pin "3") (pinfunction "3_3") (pintype "passive"))
    )
    (net (code "36") (name "Net-(IC2A-SCK)") (class "Default")
      (node (ref "IC2") (pin "11") (pinfunction "SCK_11") (pintype "input"))
      (node (ref "IC4") (pin "11") (pinfunction "SCK_11") (pintype "input"))
      (node (ref "IC6") (pin "11") (pinfunction "SCK_11") (pintype "input"))
      (node (ref "IC8") (pin "11") (pinfunction "SCK_11") (pintype "input"))
      (node (ref "JP1") (pin "2") (pinfunction "2_2") (pintype "passive"))
    )
    (net (code "37") (name "Net-(IC2A-SER)") (class "Default")
      (node (ref "IC2") (pin "14") (pinfunction "SER_14") (pintype "input"))
      (node (ref "JP1") (pin "1") (pinfunction "1_1") (pintype "passive"))
    )
    (net (code "38") (name "Net-(IC3-ENB)") (class "Default")
      (node (ref "IC3") (pin "P$14") (pinfunction "ENB_P$14") (pintype "input"))
      (node (ref "IC4") (pin "3") (pinfunction "QD_3") (pintype "tri_state"))
    )
    (net (code "39") (name "Net-(IC3-IN3)") (class "Default")
      (node (ref "IC3") (pin "P$13") (pinfunction "IN3_P$13") (pintype "input"))
      (node (ref "IC4") (pin "4") (pinfunction "QE_4") (pintype "tri_state"))
    )
    (net (code "40") (name "Net-(IC3-IN4)") (class "Default")
      (node (ref "IC3") (pin "P$15") (pinfunction "IN4_P$15") (pintype "input"))
      (node (ref "IC4") (pin "2") (pinfunction "QC_2") (pintype "tri_state"))
    )
    (net (code "41") (name "Net-(IC4A-QH*)") (class "Default")
      (node (ref "IC4") (pin "9") (pinfunction "QH*_9") (pintype "tri_state"))
      (node (ref "IC6") (pin "14") (pinfunction "SER_14") (pintype "input"))
    )
    (net (code "42") (name "Net-(IC5-ENB)") (class "Default")
      (node (ref "IC5") (pin "P$14") (pinfunction "ENB_P$14") (pintype "input"))
      (node (ref "IC6") (pin "3") (pinfunction "QD_3") (pintype "tri_state"))
    )
    (net (code "43") (name "Net-(IC5-IN3)") (class "Default")
      (node (ref "IC5") (pin "P$13") (pinfunction "IN3_P$13") (pintype "input"))
      (node (ref "IC6") (pin "4") (pinfunction "QE_4") (pintype "tri_state"))
    )
    (net (code "44") (name "Net-(IC5-IN4)") (class "Default")
      (node (ref "IC5") (pin "P$15") (pinfunction "IN4_P$15") (pintype "input"))
      (node (ref "IC6") (pin "2") (pinfunction "QC_2") (pintype "tri_state"))
    )
    (net (code "45") (name "Net-(IC6A-QH*)") (class "Default")
      (node (ref "IC6") (pin "9") (pinfunction "QH*_9") (pintype "tri_state"))
      (node (ref "IC8") (pin "14") (pinfunction "SER_14") (pintype "input"))
    )
    (net (code "46") (name "Net-(IC7-ENB)") (class "Default")
      (node (ref "IC7") (pin "P$14") (pinfunction "ENB_P$14") (pintype "input"))
      (node (ref "IC8") (pin "3") (pinfunction "QD_3") (pintype "tri_state"))
    )
    (net (code "47") (name "Net-(IC7-IN3)") (class "Default")
      (node (ref "IC7") (pin "P$13") (pinfunction "IN3_P$13") (pintype "input"))
      (node (ref "IC8") (pin "4") (pinfunction "QE_4") (pintype "tri_state"))
    )
    (net (code "48") (name "Net-(IC7-IN4)") (class "Default")
      (node (ref "IC7") (pin "P$15") (pinfunction "IN4_P$15") (pintype "input"))
      (node (ref "IC8") (pin "2") (pinfunction "QC_2") (pintype "tri_state"))
    )
    (net (code "49") (name "VCC") (class "Default")
      (node (ref "D1") (pin "P$1") (pinfunction "K_P$1") (pintype "bidirectional"))
      (node (ref "D13") (pin "P$1") (pinfunction "K_P$1") (pintype "bidirectional"))
      (node (ref "D14") (pin "P$1") (pinfunction "K_P$1") (pintype "bidirectional"))
      (node (ref "D15") (pin "P$1") (pinfunction "K_P$1") (pintype "bidirectional"))
      (node (ref "D16") (pin "P$1") (pinfunction "K_P$1") (pintype "bidirectional"))
      (node (ref "D2") (pin "P$1") (pinfunction "K_P$1") (pintype "bidirectional"))
      (node (ref "D21") (pin "P$1") (pinfunction "K_P$1") (pintype "bidirectional"))
      (node (ref "D22") (pin "P$1") (pinfunction "K_P$1") (pintype "bidirectional"))
      (node (ref "D23") (pin "P$1") (pinfunction "K_P$1") (pintype "bidirectional"))
      (node (ref "D24") (pin "P$1") (pinfunction "K_P$1") (pintype "bidirectional"))
      (node (ref "D29") (pin "P$1") (pinfunction "K_P$1") (pintype "bidirectional"))
      (node (ref "D3") (pin "P$1") (pinfunction "K_P$1") (pintype "bidirectional"))
      (node (ref "D30") (pin "P$1") (pinfunction "K_P$1") (pintype "bidirectional"))
      (node (ref "D31") (pin "P$1") (pinfunction "K_P$1") (pintype "bidirectional"))
      (node (ref "D32") (pin "P$1") (pinfunction "K_P$1") (pintype "bidirectional"))
      (node (ref "D4") (pin "P$1") (pinfunction "K_P$1") (pintype "bidirectional"))
      (node (ref "IC1") (pin "P$6") (pinfunction "VS_P$6") (pintype "power_in"))
      (node (ref "IC3") (pin "P$6") (pinfunction "VS_P$6") (pintype "power_in"))
      (node (ref "IC5") (pin "P$6") (pinfunction "VS_P$6") (pintype "power_in"))
      (node (ref "IC7") (pin "P$6") (pinfunction "VS_P$6") (pintype "power_in"))
      (node (ref "JP1") (pin "4") (pinfunction "4_4") (pintype "passive"))
    )
    (net (code "50") (name "unconnected-(IC1-NC1-PadP$3)") (class "Default")
      (node (ref "IC1") (pin "P$3") (pinfunction "NC1_P$3") (pintype "no_connect"))
    )
    (net (code "51") (name "unconnected-(IC1-NC2-PadP$18)") (class "Default")
      (node (ref "IC1") (pin "P$18") (pinfunction "NC2_P$18") (pintype "no_connect"))
    )
    (net (code "52") (name "unconnected-(IC2A-QA-Pad15)") (class "Default")
      (node (ref "IC2") (pin "15") (pinfunction "QA_15") (pintype "tri_state"))
    )
    (net (code "53") (name "unconnected-(IC2A-QB-Pad1)") (class "Default")
      (node (ref "IC2") (pin "1") (pinfunction "QB_1") (pintype "tri_state"))
    )
    (net (code "54") (name "unconnected-(IC3-NC1-PadP$3)") (class "Default")
      (node (ref "IC3") (pin "P$3") (pinfunction "NC1_P$3") (pintype "no_connect"))
    )
    (net (code "55") (name "unconnected-(IC3-NC2-PadP$18)") (class "Default")
      (node (ref "IC3") (pin "P$18") (pinfunction "NC2_P$18") (pintype "no_connect"))
    )
    (net (code "56") (name "unconnected-(IC4A-QA-Pad15)") (class "Default")
      (node (ref "IC4") (pin "15") (pinfunction "QA_15") (pintype "tri_state"))
    )
    (net (code "57") (name "unconnected-(IC4A-QB-Pad1)") (class "Default")
      (node (ref "IC4") (pin "1") (pinfunction "QB_1") (pintype "tri_state"))
    )
    (net (code "58") (name "unconnected-(IC5-NC1-PadP$3)") (class "Default")
      (node (ref "IC5") (pin "P$3") (pinfunction "NC1_P$3") (pintype "no_connect"))
    )
    (net (code "59") (name "unconnected-(IC5-NC2-PadP$18)") (class "Default")
      (node (ref "IC5") (pin "P$18") (pinfunction "NC2_P$18") (pintype "no_connect"))
    )
    (net (code "60") (name "unconnected-(IC6A-QA-Pad15)") (class "Default")
      (node (ref "IC6") (pin "15") (pinfunction "QA_15") (pintype "tri_state"))
    )
    (net (code "61") (name "unconnected-(IC6A-QB-Pad1)") (class "Default")
      (node (ref "IC6") (pin "1") (pinfunction "QB_1") (pintype "tri_state"))
    )
    (net (code "62") (name "unconnected-(IC7-NC1-PadP$3)") (class "Default")
      (node (ref "IC7") (pin "P$3") (pinfunction "NC1_P$3") (pintype "no_connect"))
    )
    (net (code "63") (name "unconnected-(IC7-NC2-PadP$18)") (class "Default")
      (node (ref "IC7") (pin "P$18") (pinfunction "NC2_P$18") (pintype "no_connect"))
    )
    (net (code "64") (name "unconnected-(IC8A-QA-Pad15)") (class "Default")
      (node (ref "IC8") (pin "15") (pinfunction "QA_15") (pintype "tri_state"))
    )
    (net (code "65") (name "unconnected-(IC8A-QB-Pad1)") (class "Default")
      (node (ref "IC8") (pin "1") (pinfunction "QB_1") (pintype "tri_state"))
    )
    (net (code "66") (name "unconnected-(IC8A-QH*-Pad9)") (class "Default")
      (node (ref "IC8") (pin "9") (pinfunction "QH*_9") (pintype "tri_state"))
    )
    (net (code "67") (name "unconnected-(JP2-Pad2)") (class "Default")
      (node (ref "JP2") (pin "2") (pinfunction "2_2") (pintype "passive"))
    )
  )
)
